# CONNECT.net
KiCad netlist of a schematic drawn in Altium Designer
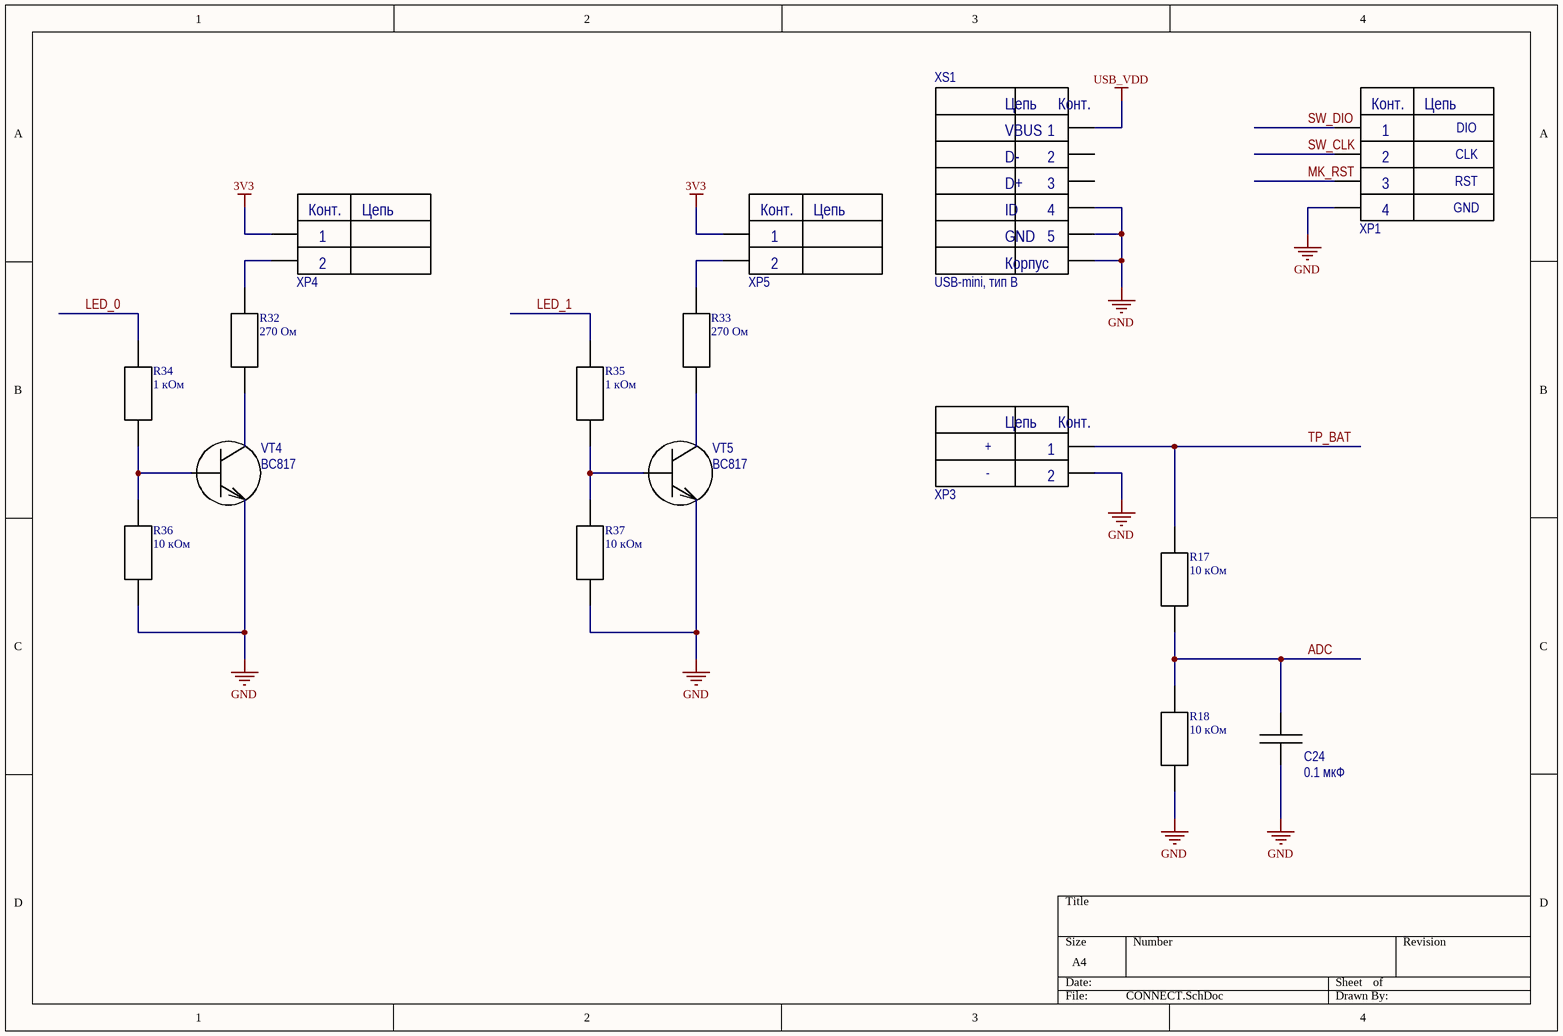
[diagram p0: CONNECT.SchDoc]

(export (version "E")
  (design (tool "Eeschema 10.0.6"))
  (components
    (comp (ref "C24")
      (value "0.1 мкФ")
      (footprint "C 1206")
      (description "SMD Capacitor 1206")
      (fields
        (field (name "TOLERANCE") "/Укажите допуск в процентах/")
        (field (name "MANUFACTURER") "/Укажите компанию-производителя/")
      )
      (libsource (lib "my_lib") (part "CAP 1206"))
    )
    (comp (ref "R17") (value "10 кОм") (footprint "RES 0805") (libsource (lib "my_lib") (part "RES 0805")))
    (comp (ref "R18") (value "10 кОм") (footprint "RES 0805") (libsource (lib "my_lib") (part "RES 0805")))
    (comp (ref "R32") (value "270 Ом") (footprint "RES 0805") (libsource (lib "my_lib") (part "RES 0805")))
    (comp (ref "R33") (value "270 Ом") (footprint "RES 0805") (libsource (lib "my_lib") (part "RES 0805")))
    (comp (ref "R34") (value "1 кОм") (footprint "RES 0805") (libsource (lib "my_lib") (part "RES 0805")))
    (comp (ref "R35") (value "1 кОм") (footprint "RES 0805") (libsource (lib "my_lib") (part "RES 0805")))
    (comp (ref "R36") (value "10 кОм") (footprint "RES 0805") (libsource (lib "my_lib") (part "RES 0805")))
    (comp (ref "R37") (value "10 кОм") (footprint "RES 0805") (libsource (lib "my_lib") (part "RES 0805")))
    (comp (ref "VT4")
      (value "BC817")
      (footprint "SOT-23")
      (description "NPN general-purpose transistor")
      (fields (field (name "MANUFACTURER") "NXP"))
      (libsource (lib "my_lib") (part "BC817"))
    )
    (comp (ref "VT5")
      (value "BC817")
      (footprint "SOT-23")
      (description "NPN general-purpose transistor")
      (fields (field (name "MANUFACTURER") "NXP"))
      (libsource (lib "my_lib") (part "BC817"))
    )
    (comp (ref "XP1")
      (value "PLD-4")
      (footprint "PLD-4")
      (description "PLD connector")
      (fields (field (name "MANUFACTURER") "NONAME"))
      (libsource (lib "my_lib") (part "PLD-4"))
    )
    (comp (ref "XP3")
      (value "PLS-2")
      (footprint "PLS-2")
      (description "PLS connector")
      (fields (field (name "MANUFACTURER") "NONAME"))
      (libsource (lib "my_lib") (part "PLS-2"))
    )
    (comp (ref "XP4")
      (value "PLS-2")
      (footprint "PLS-2")
      (description "PLS connector")
      (fields (field (name "MANUFACTURER") "NONAME"))
      (libsource (lib "my_lib") (part "PLS-2"))
    )
    (comp (ref "XP5")
      (value "PLS-2")
      (footprint "PLS-2")
      (description "PLS connector")
      (fields (field (name "MANUFACTURER") "NONAME"))
      (libsource (lib "my_lib") (part "PLS-2"))
    )
    (comp (ref "XS1")
      (value "USB-mini, тип B")
      (footprint "USB_mini_B")
      (description "USB-mini-B connector")
      (fields (field (name "MANUFACTURER") "NONAME"))
      (libsource (lib "my_lib") (part "USB-mini_B"))
    )
  )
  (nets
    (net (code "1") (name "/ADC") (class "Default")
      (node (ref "C24") (pin "1") (pinfunction "1_1") (pintype "passive"))
      (node (ref "R17") (pin "1") (pinfunction "1_1") (pintype "passive"))
      (node (ref "R18") (pin "2") (pinfunction "2_2") (pintype "passive"))
    )
    (net (code "2") (name "/LED_0") (class "Default")
      (node (ref "R34") (pin "1") (pinfunction "1_1") (pintype "passive"))
    )
    (net (code "3") (name "/LED_1") (class "Default")
      (node (ref "R35") (pin "1") (pinfunction "1_1") (pintype "passive"))
    )
    (net (code "4") (name "/MK_RST") (class "Default")
      (node (ref "XP1") (pin "3") (pinfunction "3_3") (pintype "passive"))
    )
    (net (code "5") (name "/SW_CLK") (class "Default")
      (node (ref "XP1") (pin "2") (pinfunction "2_2") (pintype "passive"))
    )
    (net (code "6") (name "/SW_DIO") (class "Default")
      (node (ref "XP1") (pin "1") (pinfunction "1_1") (pintype "passive"))
    )
    (net (code "7") (name "/TP_BAT") (class "Default")
      (node (ref "R17") (pin "2") (pinfunction "2_2") (pintype "passive"))
      (node (ref "XP3") (pin "1") (pinfunction "1_1") (pintype "passive"))
    )
    (net (code "8") (name "3V3") (class "Default")
      (node (ref "XP4") (pin "1") (pinfunction "1_1") (pintype "passive"))
      (node (ref "XP5") (pin "1") (pinfunction "1_1") (pintype "passive"))
    )
    (net (code "9") (name "GND") (class "Default")
      (node (ref "C24") (pin "2") (pinfunction "2_2") (pintype "passive"))
      (node (ref "R18") (pin "1") (pinfunction "1_1") (pintype "passive"))
      (node (ref "R36") (pin "2") (pinfunction "2_2") (pintype "passive"))
      (node (ref "R37") (pin "2") (pinfunction "2_2") (pintype "passive"))
      (node (ref "VT4") (pin "2") (pinfunction "E_2") (pintype "passive"))
      (node (ref "VT5") (pin "2") (pinfunction "E_2") (pintype "passive"))
      (node (ref "XP1") (pin "4") (pinfunction "4_4") (pintype "passive"))
      (node (ref "XP3") (pin "2") (pinfunction "2_2") (pintype "passive"))
      (node (ref "XS1") (pin "0") (pinfunction "0_0") (pintype "passive"))
      (node (ref "XS1") (pin "4") (pinfunction "CASE_4") (pintype "passive"))
      (node (ref "XS1") (pin "5") (pinfunction "GND_5") (pintype "passive"))
    )
    (net (code "10") (name "Net-(R32-Pad1)") (class "Default")
      (node (ref "R32") (pin "1") (pinfunction "1_1") (pintype "passive"))
      (node (ref "XP4") (pin "2") (pinfunction "2_2") (pintype "passive"))
    )
    (net (code "11") (name "Net-(R33-Pad1)") (class "Default")
      (node (ref "R33") (pin "1") (pinfunction "1_1") (pintype "passive"))
      (node (ref "XP5") (pin "2") (pinfunction "2_2") (pintype "passive"))
    )
    (net (code "12") (name "Net-(VT4-B)") (class "Default")
      (node (ref "R34") (pin "2") (pinfunction "2_2") (pintype "passive"))
      (node (ref "R36") (pin "1") (pinfunction "1_1") (pintype "passive"))
      (node (ref "VT4") (pin "1") (pinfunction "B_1") (pintype "passive"))
    )
    (net (code "13") (name "Net-(VT4-C)") (class "Default")
      (node (ref "R32") (pin "2") (pinfunction "2_2") (pintype "passive"))
      (node (ref "VT4") (pin "3") (pinfunction "C_3") (pintype "passive"))
    )
    (net (code "14") (name "Net-(VT5-B)") (class "Default")
      (node (ref "R35") (pin "2") (pinfunction "2_2") (pintype "passive"))
      (node (ref "R37") (pin "1") (pinfunction "1_1") (pintype "passive"))
      (node (ref "VT5") (pin "1") (pinfunction "B_1") (pintype "passive"))
    )
    (net (code "15") (name "Net-(VT5-C)") (class "Default")
      (node (ref "R33") (pin "2") (pinfunction "2_2") (pintype "passive"))
      (node (ref "VT5") (pin "3") (pinfunction "C_3") (pintype "passive"))
    )
    (net (code "16") (name "USB_VDD") (class "Default")
      (node (ref "XS1") (pin "1") (pinfunction "VBUS_1") (pintype "passive"))
    )
    (net (code "17") (name "unconnected-(XS1-D+-Pad3)") (class "Default")
      (node (ref "XS1") (pin "3") (pinfunction "D+_3") (pintype "passive"))
    )
    (net (code "18") (name "unconnected-(XS1-D--Pad2)") (class "Default")
      (node (ref "XS1") (pin "2") (pinfunction "D-_2") (pintype "passive"))
    )
  )
)
